# Sensors.net
KiCad netlist of a schematic drawn in Altium Designer
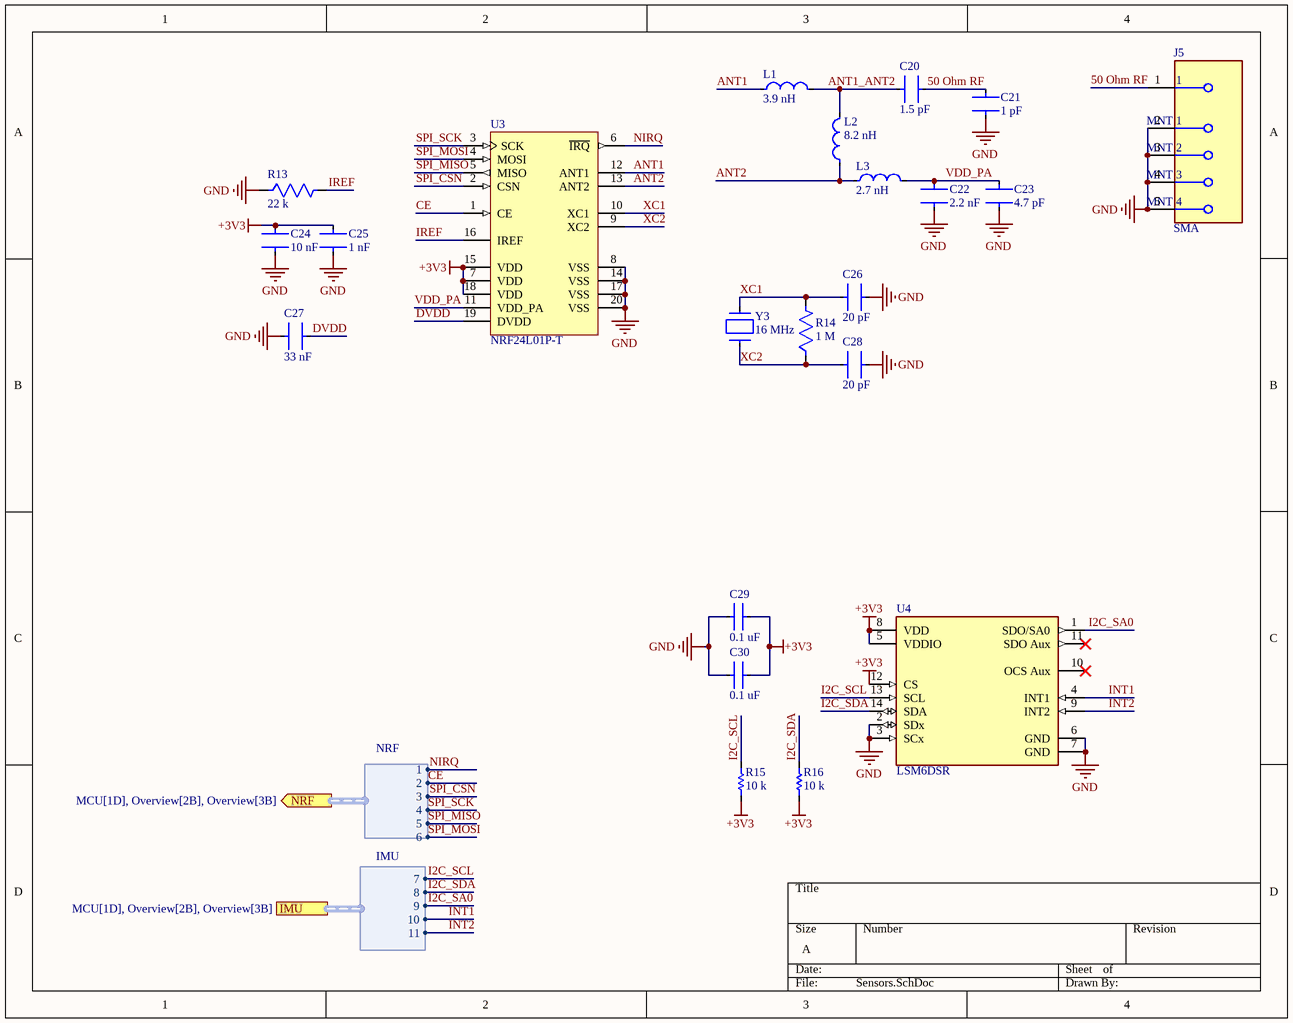
[diagram p0: Sensors.SchDoc]

(export (version "E")
  (design (tool "Eeschema 10.0.6"))
  (components
    (comp (ref "C20")
      (value "1.5 pF")
      (footprint "1_5pF_0402_Capacitor")
      (fields
        (field (name "MANUFACTURER") "Murata")
        (field (name "MANUFACTURER PART NUMBER") "GJM1555C1H1R5BB01D")
      )
      (libsource (lib "V2SchLib") (part "1_5pF_0402_Capacitor"))
    )
    (comp (ref "C21")
      (value "1 pF")
      (footprint "1pF_0402_Capacitor")
      (fields
        (field (name "MANUFACTURER") "Murata")
        (field (name "MANUFACTURER PART NUMBER") "GJM1555C1H1R0WB01D")
      )
      (libsource (lib "V2SchLib") (part "1pF_0402_Capacitor"))
    )
    (comp (ref "C22")
      (value "2.2 nF")
      (footprint "2_2nF_0402_Capacitor")
      (fields
        (field (name "MANUFACTURER") "Yageo")
        (field (name "MANUFACTURER PART NUMBER") "CC0402KRX7R9BB222")
      )
      (libsource (lib "V2SchLib") (part "2_2nF_0402_Capacitor"))
    )
    (comp (ref "C23")
      (value "4.7 pF")
      (footprint "4_7pF_0402_Capacitor")
      (fields
        (field (name "MANUFACTURER") "Murata")
        (field (name "MANUFACTURER PART NUMBER") "GJM1555C1H4R7CB01D")
      )
      (libsource (lib "V2SchLib") (part "4_7pF_0402_Capacitor"))
    )
    (comp (ref "C24")
      (value "10 nF")
      (footprint "10nF_0402_Capacitor")
      (fields
        (field (name "MANUFACTURER") "Yageo")
        (field (name "MANUFACTURER PART NUMBER") "CC0402KRX7R7BB103")
      )
      (libsource (lib "V2SchLib") (part "10nF_0402_Capacitor"))
    )
    (comp (ref "C25")
      (value "1 nF")
      (footprint "1nF_0402_Capacitor")
      (fields
        (field (name "MANUFACTURER") "Murata")
        (field (name "MANUFACTURER PART NUMBER") "GRM1555C1H102JA01D")
      )
      (libsource (lib "V2SchLib") (part "1nF_0402_Capacitor"))
    )
    (comp (ref "C26")
      (value "20 pF")
      (footprint "20pF_0402_Capacitor")
      (fields
        (field (name "MANUFACTURER") "Murata")
        (field (name "MANUFACTURER PART NUMBER") "GJM1555C1H200JB01D")
      )
      (libsource (lib "V2SchLib") (part "20pF_0402_Capacitor"))
    )
    (comp (ref "C27")
      (value "33 nF")
      (footprint "33nF_0402_Capacitor")
      (fields
        (field (name "MANUFACTURER") "Murata")
        (field (name "MANUFACTURER PART NUMBER") "GRM155R71E333KA88D")
      )
      (libsource (lib "V2SchLib") (part "33nF_0402_Capacitor"))
    )
    (comp (ref "C28")
      (value "20 pF")
      (footprint "20pF_0402_Capacitor")
      (fields
        (field (name "MANUFACTURER") "Murata")
        (field (name "MANUFACTURER PART NUMBER") "GJM1555C1H200JB01D")
      )
      (libsource (lib "V2SchLib") (part "20pF_0402_Capacitor"))
    )
    (comp (ref "C29")
      (value "0.1 uF")
      (footprint "0_1uF_0603_Capacitor")
      (fields
        (field (name "MANUFACTURER") "Murata")
        (field (name "MANUFACTURER PART NUMBER") "GCM188L81H104KA57D")
      )
      (libsource (lib "V2SchLib") (part "0_1uF_0603_Capacitor"))
    )
    (comp (ref "C30")
      (value "0.1 uF")
      (footprint "0_1uF_0603_Capacitor")
      (fields
        (field (name "MANUFACTURER") "Murata")
        (field (name "MANUFACTURER PART NUMBER") "GCM188L81H104KA57D")
      )
      (libsource (lib "V2SchLib") (part "0_1uF_0603_Capacitor"))
    )
    (comp (ref "J5")
      (value "SMA")
      (footprint "SMA_Connector")
      (fields (field (name "MANUFACTURER") "Molex") (field (name "MANUFACTURER PART NUMBER") "73251-1350"))
      (libsource (lib "V2SchLib") (part "SMA_Connector"))
    )
    (comp (ref "L1")
      (value "3.9 nH")
      (footprint "3_9nH_0402_Inductor")
      (description "General Purpose Inductor, 0.0039uH, 2.564%, 1 Element, SMD, 0402, LQW15AN3N9B80D")
      (fields
        (field (name "MANUFACTURER") "Murata")
        (field (name "MANUFACTURER PART NUMBER") "LQW15AN3N9B80D")
      )
      (libsource (lib "V2SchLib") (part "3_9nH_0402_Inductor"))
    )
    (comp (ref "L2")
      (value "8.2 nH")
      (footprint "8_2nH_0402_Inductor")
      (description "General Purpose Inductor, 0.0082uH, 2%, 1 Element, Alumina-Core, SMD, 0402, LQW15AN8N2G00D")
      (fields
        (field (name "MANUFACTURER") "Murata")
        (field (name "MANUFACTURER PART NUMBER") "LQW15AN8N2G00D")
      )
      (libsource (lib "V2SchLib") (part "8_2nH_0402_Inductor"))
    )
    (comp (ref "L3")
      (value "2.7 nH")
      (footprint "2_7nH_0402_Inductor")
      (description "General Purpose Inductor, 0.0027uH, 18.519%, 1 Element, Alumina-Core, SMD, 0402, LQW15AN2N7D00D")
      (fields
        (field (name "MANUFACTURER") "Murata")
        (field (name "MANUFACTURER PART NUMBER") "LQW15AN2N7D00D")
      )
      (libsource (lib "V2SchLib") (part "2_7nH_0402_Inductor"))
    )
    (comp (ref "R13")
      (value "22 k")
      (footprint "22k_0402_Resistor")
      (fields
        (field (name "MANUFACTURER") "Vishay Dale")
        (field (name "MANUFACTURER PART NUMBER") "CRCW040222K0JNED")
        (field (name "TOLERANCE") "5%")
      )
      (libsource (lib "V2SchLib") (part "22k_0402_Resistor"))
    )
    (comp (ref "R14")
      (value "1 M")
      (footprint "1M_0402_Resistor")
      (fields
        (field (name "MANUFACTURER") "Vishay")
        (field (name "MANUFACTURER PART NUMBER") "CRCW04021M00FKED")
        (field (name "TOLERANCE") "1%")
      )
      (libsource (lib "V2SchLib") (part "1M_0402_Resistor"))
    )
    (comp (ref "R15")
      (value "10 k")
      (footprint "10k_0603_Resistor")
      (fields
        (field (name "MANUFACTURER") "Yageo")
        (field (name "MANUFACTURER PART NUMBER") "RT0603BRD1010KL")
        (field (name "TOLERANCE") "0.1%")
      )
      (libsource (lib "V2SchLib") (part "10k_0603_Resistor"))
    )
    (comp (ref "R16")
      (value "10 k")
      (footprint "10k_0603_Resistor")
      (fields
        (field (name "MANUFACTURER") "Yageo")
        (field (name "MANUFACTURER PART NUMBER") "RT0603BRD1010KL")
        (field (name "TOLERANCE") "0.1%")
      )
      (libsource (lib "V2SchLib") (part "10k_0603_Resistor"))
    )
    (comp (ref "U3")
      (value "NRF24L01P-T")
      (footprint "nRF_Transceiver")
      (description "Telecom IC, PQCC20, NRF24L01P-T")
      (fields (field (name "MANUFACTURER") "Nordic Semiconductor"))
      (libsource (lib "V2SchLib") (part "nRF_Transceiver"))
    )
    (comp (ref "U4")
      (value "LSM6DSR")
      (footprint "IMU")
      (description "Accelerometer, LSM6DSR")
      (fields
        (field (name "MANUFACTURER") "STMicroelectronics")
        (field (name "MANUFACTURER PART NUMBER") "LSM6DSRTR")
      )
      (libsource (lib "V2SchLib") (part "IMU"))
    )
    (comp (ref "Y3")
      (value "16 MHz")
      (footprint "16MHz_Oscillator")
      (fields
        (field (name "MANUFACTURER") "Abracon")
        (field (name "MANUFACTURER PART NUMBER") "ABM7-16.000MHZ-D2Y-T")
      )
      (libsource (lib "V2SchLib") (part "16MHz_Oscillator"))
    )
  )
  (nets
    (net (code "3") (name "+3V3") (class "Default")
      (node (ref "C24") (pin "1") (pinfunction "1_1") (pintype "passive"))
      (node (ref "C25") (pin "1") (pinfunction "1_1") (pintype "passive"))
      (node (ref "C29") (pin "1") (pinfunction "1_1") (pintype "passive"))
      (node (ref "C30") (pin "1") (pinfunction "1_1") (pintype "passive"))
      (node (ref "R15") (pin "1") (pinfunction "1_1") (pintype "passive"))
      (node (ref "R16") (pin "1") (pinfunction "1_1") (pintype "passive"))
      (node (ref "U3") (pin "15") (pinfunction "VDD_15") (pintype "power_in"))
      (node (ref "U3") (pin "18") (pinfunction "VDD_18") (pintype "power_in"))
      (node (ref "U3") (pin "7") (pinfunction "VDD_7") (pintype "power_in"))
      (node (ref "U4") (pin "12") (pinfunction "CS_12") (pintype "input"))
      (node (ref "U4") (pin "5") (pinfunction "VDDIO_5") (pintype "power_in"))
      (node (ref "U4") (pin "8") (pinfunction "VDD_8") (pintype "power_in"))
    )
    (net (code "4") (name "/50 Ohm RF") (class "Default")
      (node (ref "C20") (pin "1") (pinfunction "1_1") (pintype "passive"))
      (node (ref "C21") (pin "1") (pinfunction "1_1") (pintype "passive"))
      (node (ref "J5") (pin "1") (pinfunction "1_1") (pintype "passive"))
    )
    (net (code "5") (name "/ANT1") (class "Default")
      (node (ref "L1") (pin "1") (pinfunction "1_1") (pintype "passive"))
      (node (ref "U3") (pin "12") (pinfunction "ANT1_12") (pintype "passive"))
    )
    (net (code "6") (name "/ANT1_ANT2") (class "Default")
      (node (ref "C20") (pin "2") (pinfunction "2_2") (pintype "passive"))
      (node (ref "L1") (pin "2") (pinfunction "2_2") (pintype "passive"))
      (node (ref "L2") (pin "2") (pinfunction "2_2") (pintype "passive"))
    )
    (net (code "7") (name "/ANT2") (class "Default")
      (node (ref "L2") (pin "1") (pinfunction "1_1") (pintype "passive"))
      (node (ref "L3") (pin "1") (pinfunction "1_1") (pintype "passive"))
      (node (ref "U3") (pin "13") (pinfunction "ANT2_13") (pintype "passive"))
    )
    (net (code "8") (name "/CE") (class "Default")
      (node (ref "U3") (pin "1") (pinfunction "CE_1") (pintype "input"))
    )
    (net (code "9") (name "/DVDD") (class "Default")
      (node (ref "C27") (pin "1") (pinfunction "1_1") (pintype "passive"))
      (node (ref "U3") (pin "19") (pinfunction "DVDD_19") (pintype "power_in"))
    )
    (net (code "10") (name "/I2C_SA0") (class "Default")
      (node (ref "U4") (pin "1") (pinfunction "SDO/SA0_1") (pintype "output"))
    )
    (net (code "11") (name "/I2C_SCL") (class "Default")
      (node (ref "R15") (pin "2") (pinfunction "2_2") (pintype "passive"))
      (node (ref "U4") (pin "13") (pinfunction "SCL_13") (pintype "input"))
    )
    (net (code "12") (name "/I2C_SDA") (class "Default")
      (node (ref "R16") (pin "2") (pinfunction "2_2") (pintype "passive"))
      (node (ref "U4") (pin "14") (pinfunction "SDA_14") (pintype "bidirectional"))
    )
    (net (code "13") (name "/INT1") (class "Default")
      (node (ref "U4") (pin "4") (pinfunction "INT1_4") (pintype "input"))
    )
    (net (code "14") (name "/INT2") (class "Default")
      (node (ref "U4") (pin "9") (pinfunction "INT2_9") (pintype "input"))
    )
    (net (code "15") (name "/IREF") (class "Default")
      (node (ref "R13") (pin "2") (pinfunction "2_2") (pintype "passive"))
      (node (ref "U3") (pin "16") (pinfunction "IREF_16") (pintype "passive"))
    )
    (net (code "16") (name "/NIRQ") (class "Default")
      (node (ref "U3") (pin "6") (pinfunction "~{IRQ}_6") (pintype "output"))
    )
    (net (code "17") (name "/SPI_CSN") (class "Default")
      (node (ref "U3") (pin "2") (pinfunction "CSN_2") (pintype "input"))
    )
    (net (code "18") (name "/SPI_MISO") (class "Default")
      (node (ref "U3") (pin "5") (pinfunction "MISO_5") (pintype "output"))
    )
    (net (code "19") (name "/SPI_MOSI") (class "Default")
      (node (ref "U3") (pin "4") (pinfunction "MOSI_4") (pintype "input"))
    )
    (net (code "20") (name "/SPI_SCK") (class "Default")
      (node (ref "U3") (pin "3") (pinfunction "SCK_3") (pintype "input"))
    )
    (net (code "21") (name "/VDD_PA") (class "Default")
      (node (ref "C22") (pin "1") (pinfunction "1_1") (pintype "passive"))
      (node (ref "C23") (pin "1") (pinfunction "1_1") (pintype "passive"))
      (node (ref "L3") (pin "2") (pinfunction "2_2") (pintype "passive"))
      (node (ref "U3") (pin "11") (pinfunction "VDD_PA_11") (pintype "power_in"))
    )
    (net (code "22") (name "/XC1") (class "Default")
      (node (ref "C26") (pin "2") (pinfunction "2_2") (pintype "passive"))
      (node (ref "R14") (pin "2") (pinfunction "2_2") (pintype "passive"))
      (node (ref "U3") (pin "10") (pinfunction "XC1_10") (pintype "passive"))
      (node (ref "Y3") (pin "2") (pinfunction "2_2") (pintype "passive"))
    )
    (net (code "23") (name "/XC2") (class "Default")
      (node (ref "C28") (pin "2") (pinfunction "2_2") (pintype "passive"))
      (node (ref "R14") (pin "1") (pinfunction "1_1") (pintype "passive"))
      (node (ref "U3") (pin "9") (pinfunction "XC2_9") (pintype "passive"))
      (node (ref "Y3") (pin "1") (pinfunction "1_1") (pintype "passive"))
    )
    (net (code "26") (name "GND") (class "Default")
      (node (ref "C21") (pin "2") (pinfunction "2_2") (pintype "passive"))
      (node (ref "C22") (pin "2") (pinfunction "2_2") (pintype "passive"))
      (node (ref "C23") (pin "2") (pinfunction "2_2") (pintype "passive"))
      (node (ref "C24") (pin "2") (pinfunction "2_2") (pintype "passive"))
      (node (ref "C25") (pin "2") (pinfunction "2_2") (pintype "passive"))
      (node (ref "C26") (pin "1") (pinfunction "1_1") (pintype "passive"))
      (node (ref "C27") (pin "2") (pinfunction "2_2") (pintype "passive"))
      (node (ref "C28") (pin "1") (pinfunction "1_1") (pintype "passive"))
      (node (ref "C29") (pin "2") (pinfunction "2_2") (pintype "passive"))
      (node (ref "C30") (pin "2") (pinfunction "2_2") (pintype "passive"))
      (node (ref "J5") (pin "2") (pinfunction "MNT_1_2") (pintype "passive"))
      (node (ref "J5") (pin "3") (pinfunction "MNT_2_3") (pintype "passive"))
      (node (ref "J5") (pin "4") (pinfunction "MNT_3_4") (pintype "passive"))
      (node (ref "J5") (pin "5") (pinfunction "MNT_4_5") (pintype "passive"))
      (node (ref "R13") (pin "1") (pinfunction "1_1") (pintype "passive"))
      (node (ref "U3") (pin "14") (pinfunction "VSS_14") (pintype "power_in"))
      (node (ref "U3") (pin "17") (pinfunction "VSS_17") (pintype "power_in"))
      (node (ref "U3") (pin "20") (pinfunction "VSS_20") (pintype "power_in"))
      (node (ref "U3") (pin "8") (pinfunction "VSS_8") (pintype "power_in"))
      (node (ref "U4") (pin "2") (pinfunction "SDx_2") (pintype "bidirectional"))
      (node (ref "U4") (pin "3") (pinfunction "SCx_3") (pintype "input"))
      (node (ref "U4") (pin "6") (pinfunction "GND_6") (pintype "power_in"))
      (node (ref "U4") (pin "7") (pinfunction "GND_7") (pintype "power_in"))
    )
    (net (code "27") (name "unconnected-(U4-OCS_Aux-Pad10)") (class "Default")
      (node (ref "U4") (pin "10") (pinfunction "OCS_Aux_10") (pintype "passive+no_connect"))
    )
    (net (code "28") (name "unconnected-(U4-SDO_Aux-Pad11)") (class "Default")
      (node (ref "U4") (pin "11") (pinfunction "SDO_Aux_11") (pintype "output+no_connect"))
    )
  )
)
